# Open_Ephys_Isolater.net
KiCad netlist of a schematic drawn in EAGLE
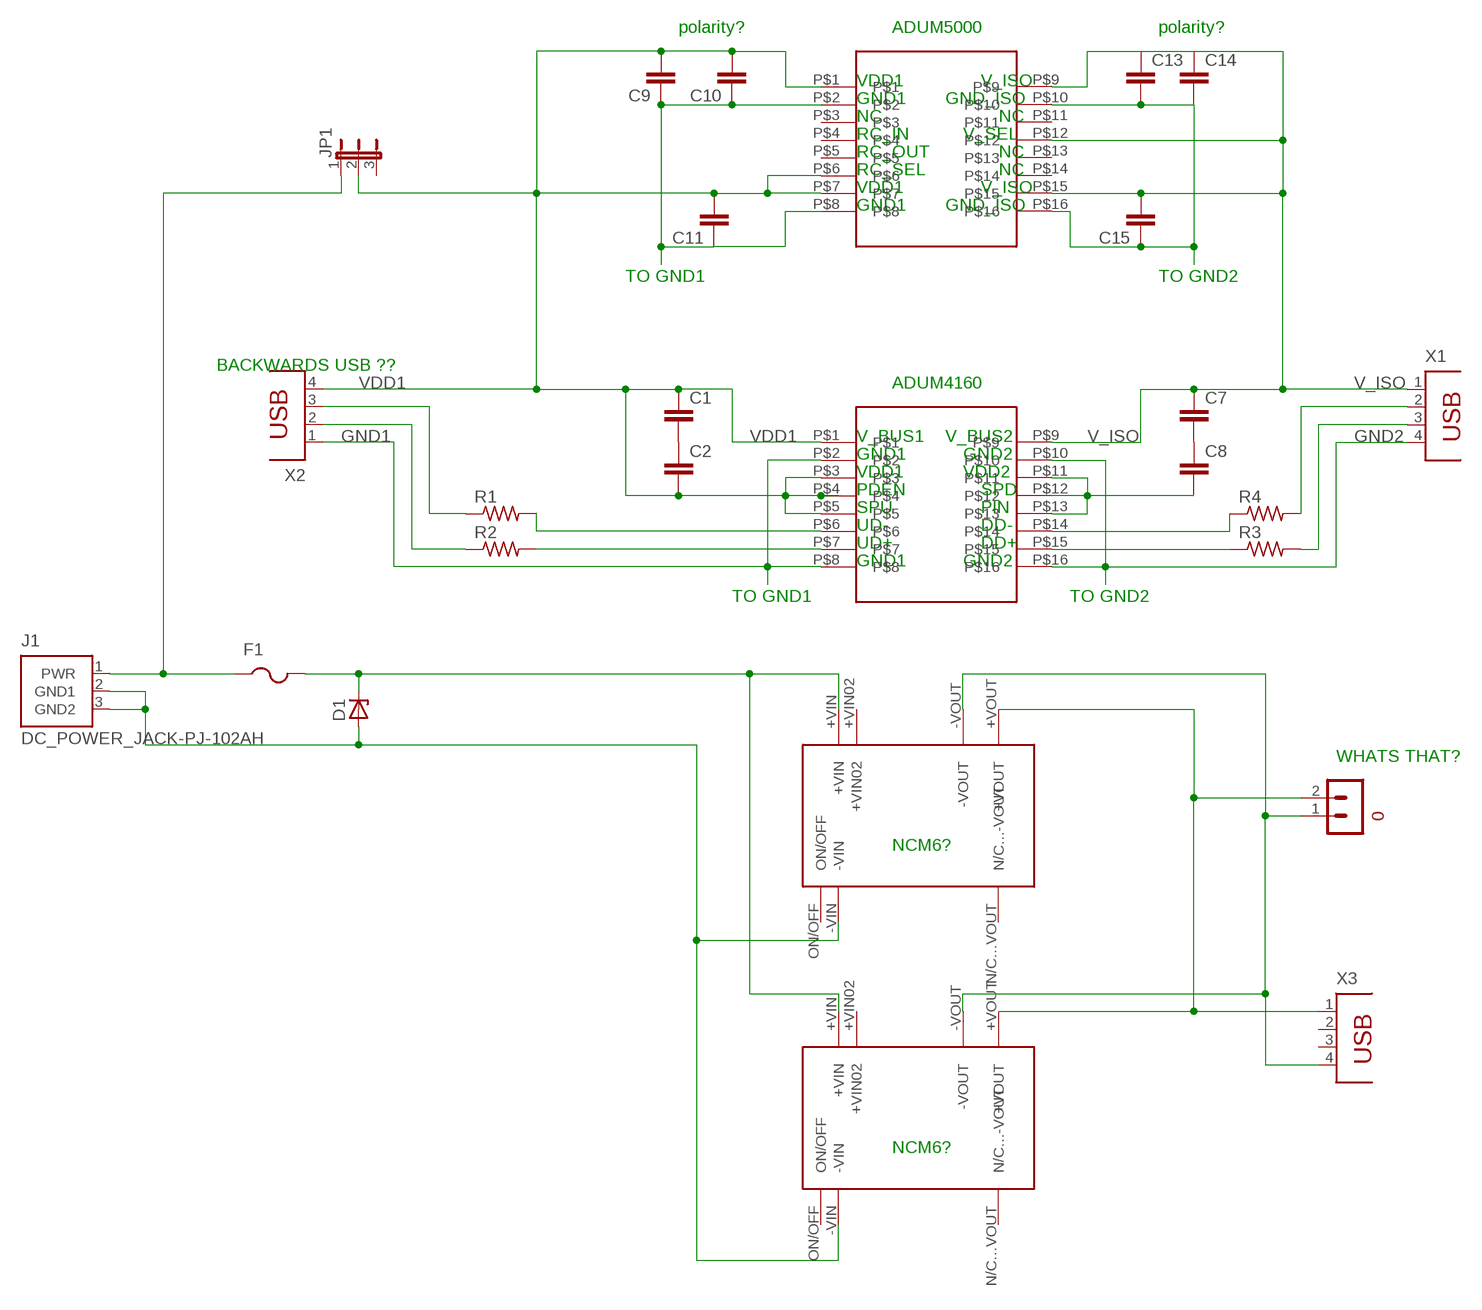
[diagram p0: schematic, sheet 1]

(export (version "E")
  (design (tool "Eeschema 10.0.6"))
  (components
    (comp (ref "C1")
      (value "C_0201")
      (footprint "eagle-import:0201")
      (libsource (lib "eagle-import") (part "C_0201"))
    )
    (comp (ref "C2")
      (value "C_0201")
      (footprint "eagle-import:0201")
      (libsource (lib "eagle-import") (part "C_0201"))
    )
    (comp (ref "C7")
      (value "C_0201")
      (footprint "eagle-import:0201")
      (libsource (lib "eagle-import") (part "C_0201"))
    )
    (comp (ref "C8")
      (value "C_0201")
      (footprint "eagle-import:0201")
      (libsource (lib "eagle-import") (part "C_0201"))
    )
    (comp (ref "C9")
      (value "C_0201")
      (footprint "eagle-import:0201")
      (libsource (lib "eagle-import") (part "C_0201"))
    )
    (comp (ref "C10")
      (value "C_0201")
      (footprint "eagle-import:0201")
      (libsource (lib "eagle-import") (part "C_0201"))
    )
    (comp (ref "C11")
      (value "C_0201")
      (footprint "eagle-import:0201")
      (libsource (lib "eagle-import") (part "C_0201"))
    )
    (comp (ref "C13")
      (value "C_0201")
      (footprint "eagle-import:0201")
      (libsource (lib "eagle-import") (part "C_0201"))
    )
    (comp (ref "C14")
      (value "C_0201")
      (footprint "eagle-import:0201")
      (libsource (lib "eagle-import") (part "C_0201"))
    )
    (comp (ref "C15")
      (value "C_0201")
      (footprint "eagle-import:0201")
      (libsource (lib "eagle-import") (part "C_0201"))
    )
    (comp (ref "D1")
      (value "ZENER-DIODESMB")
      (footprint "eagle-import:SMB")
      (libsource (lib "eagle-import") (part "ZENER-DIODESMB"))
    )
    (comp (ref "F1")
      (value "PTCFUSE-1206")
      (footprint "eagle-import:R1206")
      (libsource (lib "eagle-import") (part "PTCFUSE-1206"))
    )
    (comp (ref "J1")
      (value "DC_POWER_JACK-PJ-102AH")
      (footprint "eagle-import:PJ-102AH")
      (libsource (lib "eagle-import") (part "DC_POWER_JACK-PJ-102AH"))
    )
    (comp (ref "JP1")
      (value "JP2E")
      (footprint "eagle-import:JP2")
      (libsource (lib "eagle-import") (part "JP2E"))
    )
    (comp (ref "R1")
      (value "R-US_R2512")
      (footprint "eagle-import:R2512")
      (libsource (lib "eagle-import") (part "R-US_R2512"))
    )
    (comp (ref "R2")
      (value "R-US_R2512")
      (footprint "eagle-import:R2512")
      (libsource (lib "eagle-import") (part "R-US_R2512"))
    )
    (comp (ref "R3")
      (value "R-US_R2512")
      (footprint "eagle-import:R2512")
      (libsource (lib "eagle-import") (part "R-US_R2512"))
    )
    (comp (ref "R4")
      (value "R-US_R2512")
      (footprint "eagle-import:R2512")
      (libsource (lib "eagle-import") (part "R-US_R2512"))
    )
    (comp (ref "S1")
      (value "TERMINAL_BLOCK_2-3.5MM-5V")
      (footprint "eagle-import:TERMINAL_BLOCK_3.5MM_2_5V")
      (libsource (lib "eagle-import") (part "TERMINAL_BLOCK_2-3.5MM-5V"))
    )
    (comp (ref "U$1")
      (value "ADUM4160")
      (footprint "eagle-import:ADUM4160")
      (libsource (lib "eagle-import") (part "ADUM4160"))
    )
    (comp (ref "U$2")
      (value "ADUM4160")
      (footprint "eagle-import:ADUM4160")
      (libsource (lib "eagle-import") (part "ADUM4160"))
    )
    (comp (ref "U$3")
      (value "NCM6S0505EC")
      (footprint "eagle-import:NCM6S0505EC")
      (libsource (lib "eagle-import") (part "NCM6S0505EC"))
    )
    (comp (ref "U$4")
      (value "NCM6S0505EC")
      (footprint "eagle-import:NCM6S0505EC")
      (libsource (lib "eagle-import") (part "NCM6S0505EC"))
    )
    (comp (ref "X1")
      (value "PN87520")
      (footprint "eagle-import:PN87520")
      (libsource (lib "eagle-import") (part "PN87520"))
    )
    (comp (ref "X2")
      (value "PN61729")
      (footprint "eagle-import:PN61729")
      (libsource (lib "eagle-import") (part "PN61729"))
    )
    (comp (ref "X3")
      (value "PN87520")
      (footprint "eagle-import:PN87520")
      (libsource (lib "eagle-import") (part "PN87520"))
    )
  )
  (nets
    (net (code "1") (name "/GND1") (class "Default")
      (node (ref "C10") (pin "1") (pinfunction "1_1") (pintype "passive"))
      (node (ref "C11") (pin "1") (pinfunction "1_1") (pintype "passive"))
      (node (ref "C9") (pin "1") (pinfunction "1_1") (pintype "passive"))
      (node (ref "D1") (pin "A") (pinfunction "A_A") (pintype "passive"))
      (node (ref "J1") (pin "2") (pinfunction "GND1_2") (pintype "power_in"))
      (node (ref "J1") (pin "3") (pinfunction "GND2_3") (pintype "power_in"))
      (node (ref "U$1") (pin "P$2") (pinfunction "P$2_P$2") (pintype "bidirectional"))
      (node (ref "U$1") (pin "P$8") (pinfunction "P$8_P$8") (pintype "bidirectional"))
      (node (ref "U$2") (pin "P$2") (pinfunction "P$2_P$2") (pintype "bidirectional"))
      (node (ref "U$2") (pin "P$8") (pinfunction "P$8_P$8") (pintype "bidirectional"))
      (node (ref "U$3") (pin "-VIN") (pinfunction "-VIN_-VIN") (pintype "bidirectional"))
      (node (ref "U$4") (pin "-VIN") (pinfunction "-VIN_-VIN") (pintype "bidirectional"))
      (node (ref "X2") (pin "1") (pinfunction "1_1") (pintype "passive"))
    )
    (net (code "2") (name "/GND2") (class "Default")
      (node (ref "C13") (pin "2") (pinfunction "2_2") (pintype "passive"))
      (node (ref "C14") (pin "2") (pinfunction "2_2") (pintype "passive"))
      (node (ref "C15") (pin "1") (pinfunction "1_1") (pintype "passive"))
      (node (ref "S1") (pin "1") (pinfunction "0_1") (pintype "passive"))
      (node (ref "U$1") (pin "P$10") (pinfunction "P$10_P$10") (pintype "bidirectional"))
      (node (ref "U$1") (pin "P$16") (pinfunction "P$16_P$16") (pintype "bidirectional"))
      (node (ref "U$2") (pin "P$10") (pinfunction "P$10_P$10") (pintype "bidirectional"))
      (node (ref "U$2") (pin "P$16") (pinfunction "P$16_P$16") (pintype "bidirectional"))
      (node (ref "U$3") (pin "-VOUT") (pinfunction "-VOUT_-VOUT") (pintype "bidirectional"))
      (node (ref "U$4") (pin "-VOUT") (pinfunction "-VOUT_-VOUT") (pintype "bidirectional"))
      (node (ref "X1") (pin "4") (pinfunction "4_4") (pintype "passive"))
      (node (ref "X3") (pin "4") (pinfunction "4_4") (pintype "passive"))
    )
    (net (code "3") (name "/VDD1") (class "Default")
      (node (ref "C1") (pin "1") (pinfunction "1_1") (pintype "passive"))
      (node (ref "C10") (pin "2") (pinfunction "2_2") (pintype "passive"))
      (node (ref "C11") (pin "2") (pinfunction "2_2") (pintype "passive"))
      (node (ref "C2") (pin "2") (pinfunction "2_2") (pintype "passive"))
      (node (ref "C9") (pin "2") (pinfunction "2_2") (pintype "passive"))
      (node (ref "JP1") (pin "2") (pinfunction "2_2") (pintype "passive"))
      (node (ref "U$1") (pin "P$1") (pinfunction "P$1_P$1") (pintype "bidirectional"))
      (node (ref "U$1") (pin "P$6") (pinfunction "P$6_P$6") (pintype "bidirectional"))
      (node (ref "U$1") (pin "P$7") (pinfunction "P$7_P$7") (pintype "bidirectional"))
      (node (ref "U$2") (pin "P$1") (pinfunction "P$1_P$1") (pintype "bidirectional"))
      (node (ref "U$2") (pin "P$3") (pinfunction "P$3_P$3") (pintype "bidirectional"))
      (node (ref "U$2") (pin "P$4") (pinfunction "P$4_P$4") (pintype "bidirectional"))
      (node (ref "U$2") (pin "P$5") (pinfunction "P$5_P$5") (pintype "bidirectional"))
      (node (ref "X2") (pin "4") (pinfunction "4_4") (pintype "passive"))
    )
    (net (code "4") (name "/V_ISO") (class "Default")
      (node (ref "C13") (pin "1") (pinfunction "1_1") (pintype "passive"))
      (node (ref "C14") (pin "1") (pinfunction "1_1") (pintype "passive"))
      (node (ref "C15") (pin "2") (pinfunction "2_2") (pintype "passive"))
      (node (ref "C7") (pin "1") (pinfunction "1_1") (pintype "passive"))
      (node (ref "U$1") (pin "P$12") (pinfunction "P$12_P$12") (pintype "bidirectional"))
      (node (ref "U$1") (pin "P$15") (pinfunction "P$15_P$15") (pintype "bidirectional"))
      (node (ref "U$1") (pin "P$9") (pinfunction "P$9_P$9") (pintype "bidirectional"))
      (node (ref "U$2") (pin "P$9") (pinfunction "P$9_P$9") (pintype "bidirectional"))
      (node (ref "X1") (pin "1") (pinfunction "1_1") (pintype "passive"))
    )
    (net (code "5") (name "Net-(C1-Pad2)") (class "Default")
      (node (ref "C1") (pin "2") (pinfunction "2_2") (pintype "passive"))
      (node (ref "C2") (pin "1") (pinfunction "1_1") (pintype "passive"))
    )
    (net (code "6") (name "Net-(C7-Pad2)") (class "Default")
      (node (ref "C7") (pin "2") (pinfunction "2_2") (pintype "passive"))
      (node (ref "C8") (pin "1") (pinfunction "1_1") (pintype "passive"))
    )
    (net (code "7") (name "Net-(C8-Pad2)") (class "Default")
      (node (ref "C8") (pin "2") (pinfunction "2_2") (pintype "passive"))
      (node (ref "U$2") (pin "P$11") (pinfunction "P$11_P$11") (pintype "bidirectional"))
      (node (ref "U$2") (pin "P$12") (pinfunction "P$12_P$12") (pintype "bidirectional"))
      (node (ref "U$2") (pin "P$13") (pinfunction "P$13_P$13") (pintype "bidirectional"))
    )
    (net (code "8") (name "Net-(D1-PadC)") (class "Default")
      (node (ref "D1") (pin "C") (pinfunction "C_C") (pintype "passive"))
      (node (ref "F1") (pin "2") (pinfunction "2_2") (pintype "passive"))
      (node (ref "U$3") (pin "+VIN") (pinfunction "+VIN_+VIN") (pintype "bidirectional"))
      (node (ref "U$4") (pin "+VIN") (pinfunction "+VIN_+VIN") (pintype "bidirectional"))
    )
    (net (code "9") (name "Net-(J1-PWR)") (class "Default")
      (node (ref "F1") (pin "1") (pinfunction "1_1") (pintype "passive"))
      (node (ref "J1") (pin "1") (pinfunction "PWR_1") (pintype "power_in"))
      (node (ref "JP1") (pin "1") (pinfunction "1_1") (pintype "passive"))
    )
    (net (code "10") (name "Net-(R1-Pad1)") (class "Default")
      (node (ref "R1") (pin "1") (pinfunction "1_1") (pintype "passive"))
      (node (ref "X2") (pin "3") (pinfunction "3_3") (pintype "passive"))
    )
    (net (code "11") (name "Net-(R1-Pad2)") (class "Default")
      (node (ref "R1") (pin "2") (pinfunction "2_2") (pintype "passive"))
      (node (ref "U$2") (pin "P$6") (pinfunction "P$6_P$6") (pintype "bidirectional"))
    )
    (net (code "12") (name "Net-(R2-Pad1)") (class "Default")
      (node (ref "R2") (pin "1") (pinfunction "1_1") (pintype "passive"))
      (node (ref "X2") (pin "2") (pinfunction "2_2") (pintype "passive"))
    )
    (net (code "13") (name "Net-(R2-Pad2)") (class "Default")
      (node (ref "R2") (pin "2") (pinfunction "2_2") (pintype "passive"))
      (node (ref "U$2") (pin "P$7") (pinfunction "P$7_P$7") (pintype "bidirectional"))
    )
    (net (code "14") (name "Net-(R3-Pad1)") (class "Default")
      (node (ref "R3") (pin "1") (pinfunction "1_1") (pintype "passive"))
      (node (ref "U$2") (pin "P$15") (pinfunction "P$15_P$15") (pintype "bidirectional"))
    )
    (net (code "15") (name "Net-(R3-Pad2)") (class "Default")
      (node (ref "R3") (pin "2") (pinfunction "2_2") (pintype "passive"))
      (node (ref "X1") (pin "3") (pinfunction "3_3") (pintype "passive"))
    )
    (net (code "16") (name "Net-(R4-Pad1)") (class "Default")
      (node (ref "R4") (pin "1") (pinfunction "1_1") (pintype "passive"))
      (node (ref "U$2") (pin "P$14") (pinfunction "P$14_P$14") (pintype "bidirectional"))
    )
    (net (code "17") (name "Net-(R4-Pad2)") (class "Default")
      (node (ref "R4") (pin "2") (pinfunction "2_2") (pintype "passive"))
      (node (ref "X1") (pin "2") (pinfunction "2_2") (pintype "passive"))
    )
    (net (code "18") (name "Net-(S1-1)") (class "Default")
      (node (ref "S1") (pin "2") (pinfunction "1_2") (pintype "passive"))
      (node (ref "U$3") (pin "+VOUT") (pinfunction "+VOUT_+VOUT") (pintype "bidirectional"))
      (node (ref "U$4") (pin "+VOUT") (pinfunction "+VOUT_+VOUT") (pintype "bidirectional"))
      (node (ref "X3") (pin "1") (pinfunction "1_1") (pintype "passive"))
    )
    (net (code "19") (name "unconnected-(JP1-Pad3)") (class "Default")
      (node (ref "JP1") (pin "3") (pinfunction "3_3") (pintype "passive"))
    )
    (net (code "20") (name "unconnected-(U$1-PadP$3)") (class "Default")
      (node (ref "U$1") (pin "P$3") (pinfunction "P$3_P$3") (pintype "bidirectional"))
    )
    (net (code "21") (name "unconnected-(U$1-PadP$4)") (class "Default")
      (node (ref "U$1") (pin "P$4") (pinfunction "P$4_P$4") (pintype "bidirectional"))
    )
    (net (code "22") (name "unconnected-(U$1-PadP$5)") (class "Default")
      (node (ref "U$1") (pin "P$5") (pinfunction "P$5_P$5") (pintype "bidirectional"))
    )
    (net (code "23") (name "unconnected-(U$1-PadP$11)") (class "Default")
      (node (ref "U$1") (pin "P$11") (pinfunction "P$11_P$11") (pintype "bidirectional"))
    )
    (net (code "24") (name "unconnected-(U$1-PadP$13)") (class "Default")
      (node (ref "U$1") (pin "P$13") (pinfunction "P$13_P$13") (pintype "bidirectional"))
    )
    (net (code "25") (name "unconnected-(U$1-PadP$14)") (class "Default")
      (node (ref "U$1") (pin "P$14") (pinfunction "P$14_P$14") (pintype "bidirectional"))
    )
    (net (code "26") (name "unconnected-(U$3-N{slash}C...-VOUT-PadN{slash}C...VOUT)") (class "Default")
      (node (ref "U$3") (pin "N/C...VOUT") (pinfunction "N/C...-VOUT_N/C...VOUT") (pintype "bidirectional"))
    )
    (net (code "27") (name "unconnected-(U$3-Pad+VIN02)") (class "Default")
      (node (ref "U$3") (pin "+VIN02") (pinfunction "+VIN02_+VIN02") (pintype "bidirectional"))
    )
    (net (code "28") (name "unconnected-(U$3-PadON{slash}OFF)") (class "Default")
      (node (ref "U$3") (pin "ON/OFF") (pinfunction "ON/OFF_ON/OFF") (pintype "bidirectional"))
    )
    (net (code "29") (name "unconnected-(U$4-N{slash}C...-VOUT-PadN{slash}C...VOUT)") (class "Default")
      (node (ref "U$4") (pin "N/C...VOUT") (pinfunction "N/C...-VOUT_N/C...VOUT") (pintype "bidirectional"))
    )
    (net (code "30") (name "unconnected-(U$4-Pad+VIN02)") (class "Default")
      (node (ref "U$4") (pin "+VIN02") (pinfunction "+VIN02_+VIN02") (pintype "bidirectional"))
    )
    (net (code "31") (name "unconnected-(U$4-PadON{slash}OFF)") (class "Default")
      (node (ref "U$4") (pin "ON/OFF") (pinfunction "ON/OFF_ON/OFF") (pintype "bidirectional"))
    )
    (net (code "32") (name "unconnected-(X3-Pad2)") (class "Default")
      (node (ref "X3") (pin "2") (pinfunction "2_2") (pintype "passive"))
    )
    (net (code "33") (name "unconnected-(X3-Pad3)") (class "Default")
      (node (ref "X3") (pin "3") (pinfunction "3_3") (pintype "passive"))
    )
  )
)
